# ESP32_module_desing.net
KiCad netlist of a schematic drawn in Altium Designer
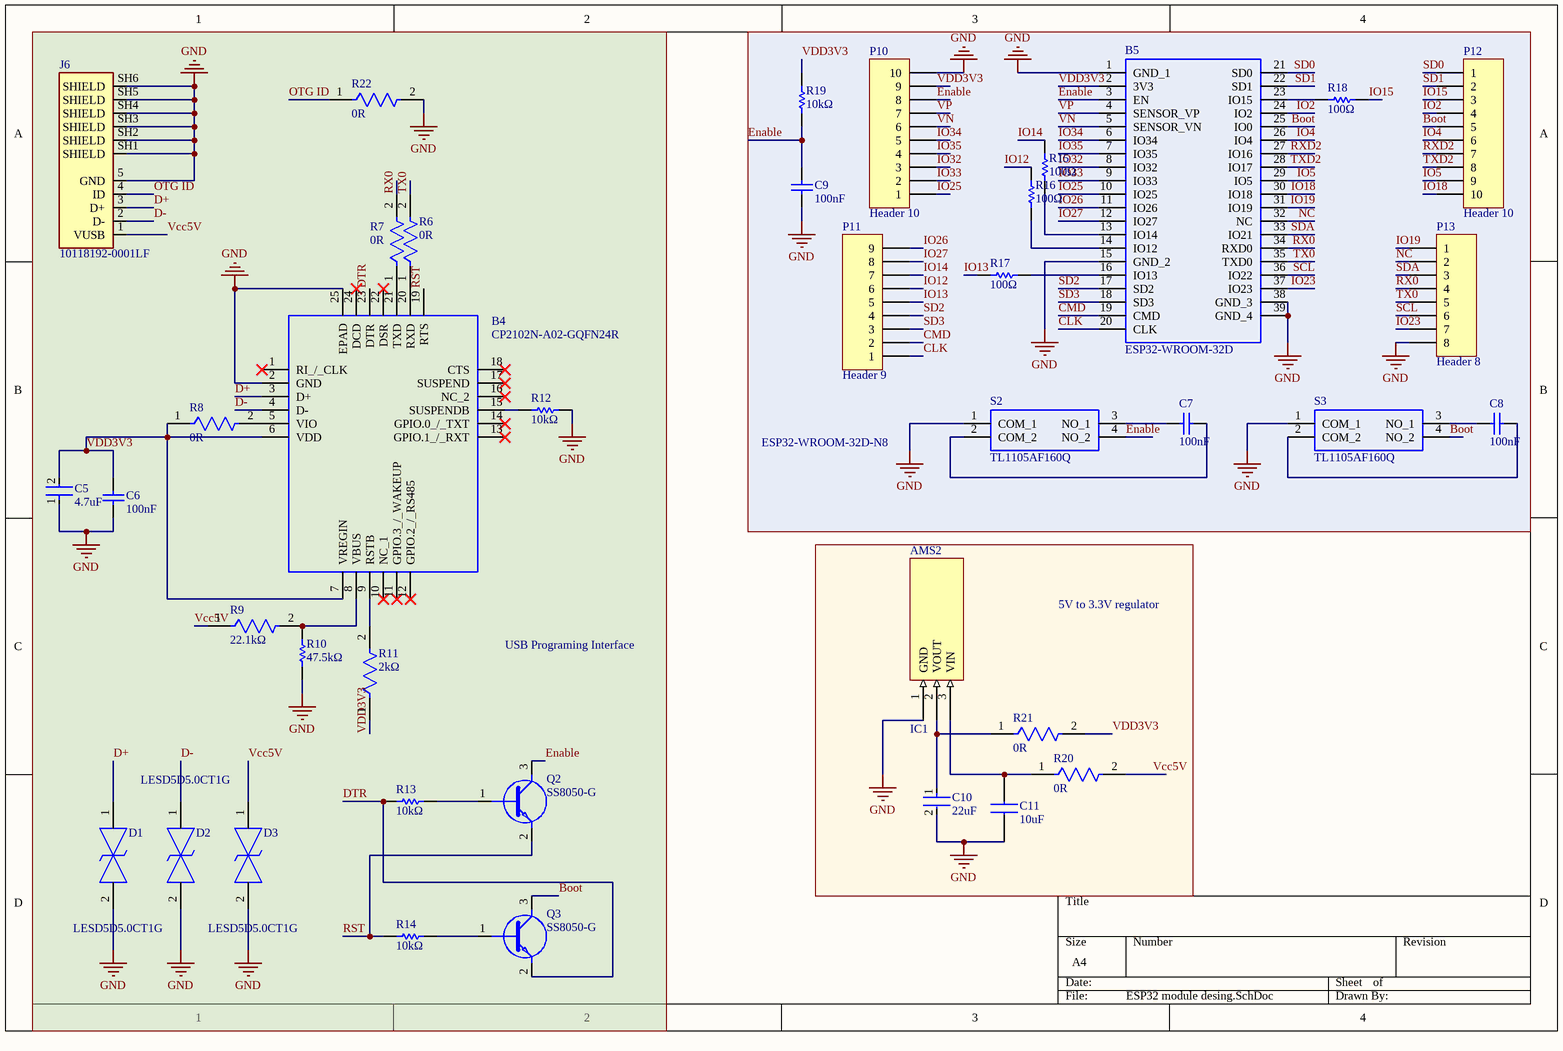
[diagram p0: ESP32 module desing.SchDoc]

(export (version "E")
  (design (tool "Eeschema 10.0.6"))
  (components
    (comp (ref "AMS2")
      (value "IC1")
      (footprint "SOT89-150P350X150-3N")
      (fields
        (field (name "MANUFACTURER") "YONGYUTAI")
        (field (name "MFR. PART #") "AMS1117-3.3")
        (field (name "LCSC PART #") "C2904742")
      )
      (libsource (lib "AMS1117-3.3") (part "IC?"))
    )
    (comp (ref "B4")
      (value "CP2102N-A02-GQFN24R")
      (footprint "QFN50P400X400X80-25N-D")
      (description "USB Interface IC USB to UART bridge - QFN24")
      (fields (field (name "MANUFACTURER") "SILICON LABS") (field (name "LCSC PART#") "C969151"))
      (libsource (lib "CP2102N-A02-GQFN24R") (part "CP2102N-A02-GQFN24R"))
    )
    (comp (ref "B5")
      (value "ESP32-WROOM-32D")
      (footprint "ESP32WROOM32D")
      (description "WiFi Modules (802.11) SMD Module, ESP32-D0WD, 32Mbits SPI flash, UART mode, PCB antenna")
      (libsource (lib "ESP32-WROOM-32D") (part "ESP32-WROOM-32D"))
    )
    (comp (ref "C5")
      (value "4.7uF")
      (footprint "FP-CL21-IPC_A")
      (description "X5R 25V 4.7uF ±10% 0805 Multilayer Ceramic Capacitors MLCC - SMD/SMT ROHS")
      (fields (field (name "LCSC PART#") "C1779") (field (name "MFR.PART #") "CL21A475KAQNNNE"))
      (libsource (lib "Altium Content Vault") (part "b4654b650e69147ec39a6b967a45e02"))
    )
    (comp (ref "C6")
      (value "100nF")
      (footprint "CAPC1050X55X23ML05T13")
      (description "X7R 100nF 16V ±10% 0402 Multilayer Ceramic Capacitors MLCC - SMD/SMT ROHS")
      (fields
        (field (name "MANUFACTURER") "Samsung Electro-Mechanics")
        (field (name "MFR.PART #") "CL05B104KO5NNNC")
      )
      (libsource (lib "Altium Content Vault") (part "CAP-NP-2"))
    )
    (comp (ref "C7")
      (value "100nF")
      (footprint "CAPC1050X55X23ML05T13")
      (description "X7R 100nF 16V ±10% 0402 Multilayer Ceramic Capacitors MLCC - SMD/SMT ROHS")
      (fields
        (field (name "MANUFACTURER") "Samsung Electro-Mechanics")
        (field (name "MFR.PART #") "CL05B104KO5NNNC")
      )
      (libsource (lib "Altium Content Vault") (part "CAP-NP-2"))
    )
    (comp (ref "C8")
      (value "100nF")
      (footprint "CAPC1050X55X23ML05T13")
      (description "X7R 100nF 16V ±10% 0402 Multilayer Ceramic Capacitors MLCC - SMD/SMT ROHS")
      (fields
        (field (name "MANUFACTURER") "Samsung Electro-Mechanics")
        (field (name "MFR.PART #") "CL05B104KO5NNNC")
      )
      (libsource (lib "Altium Content Vault") (part "CAP-NP-2"))
    )
    (comp (ref "C9")
      (value "100nF")
      (footprint "CAPC1050X55X23ML05T13")
      (description "X7R 100nF 16V ±10% 0402 Multilayer Ceramic Capacitors MLCC - SMD/SMT ROHS")
      (fields
        (field (name "MANUFACTURER") "Samsung Electro-Mechanics")
        (field (name "MFR.PART #") "CL05B104KO5NNNC")
      )
      (libsource (lib "Altium Content Vault") (part "CAP-NP-2"))
    )
    (comp (ref "C10")
      (value "22uF")
      (footprint "FP-GRM219-0_2-0_15-IPC_A")
      (description "Chip Multilayer Ceramic Capacitors for General Purpose, 0805, 22uF, X5R, 15%, 20%, 16V")
      (fields (field (name "MFR. PART #") "GRM219R61C226ME15L") (field (name "LCSC PART #") "C162295"))
      (libsource (lib "Altium Content Vault") (part "b4654b650e69147ec39a6b967a45e02"))
    )
    (comp (ref "C11")
      (value "10uF")
      (footprint "CAPC1005X70N")
      (description "6.3V 10uF X5R ±20% 0402 Multilayer Ceramic Capacitors MLCC - SMD/SMT ROHS")
      (fields
        (field (name "MANUFACTURER") "Samsung Electro-Mechanics")
        (field (name "MFR. PART #") "CL05A106MQ5NUNC")
      )
      (libsource (lib "CL05A106MQ5NUNC") (part "CL05A106MQ5NUNC"))
    )
    (comp (ref "D1")
      (value "LESD5D5.0CT1G")
      (footprint "LESD5D50CT1G")
      (description "Transient Voltage Suppressors for ESD Protection")
      (fields
        (field (name "MANUFACTURER") "UMW(Youtai Semiconductor Co., Ltd.)")
        (field (name "LCSC PART#") "C5199850")
      )
      (libsource (lib "LESD5D5.0CT1G") (part "LESD5D5.0CT1G"))
    )
    (comp (ref "D2")
      (value "LESD5D5.0CT1G")
      (footprint "LESD5D50CT1G")
      (description "Transient Voltage Suppressors for ESD Protection")
      (fields
        (field (name "MANUFACTURER") "UMW(Youtai Semiconductor Co., Ltd.)")
        (field (name "LCSC PART#") "C5199850")
      )
      (libsource (lib "LESD5D5.0CT1G") (part "LESD5D5.0CT1G"))
    )
    (comp (ref "D3")
      (value "LESD5D5.0CT1G")
      (footprint "LESD5D50CT1G")
      (description "Transient Voltage Suppressors for ESD Protection")
      (fields
        (field (name "MANUFACTURER") "UMW(Youtai Semiconductor Co., Ltd.)")
        (field (name "LCSC PART#") "C5199850")
      )
      (libsource (lib "LESD5D5.0CT1G") (part "LESD5D5.0CT1G"))
    )
    (comp (ref "J6")
      (value "10118192-0001LF")
      (footprint "AMPHENOL_10118192-0001LF")
      (description "Single Port 5 Contact Horizontal Right Angle Shielded Micro B USB 2.0 Connector")
      (fields (field (name "LCSC PART#") "C132564") (field (name "MANUFACTURER") "Amphenol ICC"))
      (libsource (lib "10118192-0001LF") (part "10118192-0001LF"))
    )
    (comp (ref "P10")
      (value "Header 10")
      (footprint "HDR1X10")
      (description "Header, 10-Pin")
      (fields (field (name "PUBLISHER") "Altium Limited"))
      (libsource (lib "Miscellaneous Connectors") (part "Header 10"))
    )
    (comp (ref "P11")
      (value "Header 9")
      (footprint "HDR1X9")
      (description "Header, 9-Pin")
      (fields (field (name "PUBLISHER") "Altium Limited"))
      (libsource (lib "Miscellaneous Connectors") (part "Header 9"))
    )
    (comp (ref "P12")
      (value "Header 10")
      (footprint "HDR1X10")
      (description "Header, 10-Pin")
      (fields (field (name "PUBLISHER") "Altium Limited"))
      (libsource (lib "") (part "Header 10_1"))
    )
    (comp (ref "P13")
      (value "Header 8")
      (footprint "HDR1X8")
      (description "Header, 8-Pin")
      (fields (field (name "PUBLISHER") "Altium Limited"))
      (libsource (lib "Miscellaneous Connectors") (part "Header 8"))
    )
    (comp (ref "Q2")
      (value "SS8050-G")
      (footprint "SOT95P240X115-3N")
      (fields
        (field (name "MANUFACTURER") "Jiangsu Changjing Electronics Technology Co., Ltd.")
        (field (name "LCSC PART#") "C164885")
      )
      (libsource (lib "SS8050-G") (part "SS8050-G"))
    )
    (comp (ref "Q3")
      (value "SS8050-G")
      (footprint "SOT95P240X115-3N")
      (fields
        (field (name "MANUFACTURER") "Jiangsu Changjing Electronics Technology Co., Ltd.")
        (field (name "LCSC PART#") "C164885")
      )
      (libsource (lib "SS8050-G") (part "SS8050-G"))
    )
    (comp (ref "R6")
      (value "0R")
      (footprint "FP-RC0402-0_4-IPC_A")
      (description "RES SMD 0 OHM JUMPER 1/16W 0402")
      (fields (field (name "MANUFACTURER") "Yageo") (field (name "LCSC PART #") "C106231"))
      (libsource (lib "Altium Content Vault") (part "1029c3af85768c4190bb7ad29bc67b5"))
    )
    (comp (ref "R7")
      (value "0R")
      (footprint "FP-RC0402-0_4-IPC_A")
      (description "RES SMD 0 OHM JUMPER 1/16W 0402")
      (fields (field (name "MANUFACTURER") "Yageo") (field (name "LCSC PART #") "C106231"))
      (libsource (lib "Altium Content Vault") (part "1029c3af85768c4190bb7ad29bc67b5"))
    )
    (comp (ref "R8")
      (value "0R")
      (footprint "FP-RC0402-0_4-IPC_A")
      (description "RES SMD 0 OHM JUMPER 1/16W 0402")
      (fields (field (name "MANUFACTURER") "Yageo") (field (name "LCSC PART #") "C106231"))
      (libsource (lib "Altium Content Vault") (part "1029c3af85768c4190bb7ad29bc67b5"))
    )
    (comp (ref "R9")
      (value "22.1kΩ")
      (footprint "FP-RC0402-0_4-IPC_B")
      (description "RES 22.1K OHM 1% 1/16W 0402")
      (fields (field (name "LCSC PART#") "C163478") (field (name "MANUFACTURER") "YAGEO"))
      (libsource (lib "Altium Content Vault") (part "1029c3af85768c4190bb7ad29bc67b5"))
    )
    (comp (ref "R10")
      (value "47.5kΩ")
      (footprint "RESC1005X40X25NL05T10")
      (fields
        (field (name "MFR.PART #") "RC0402FR-0747K5L")
        (field (name "MANUFACTURER") "YAGEO")
        (field (name "LCSC PART#") "C137974")
      )
      (libsource (lib "Altium Content Vault") (part "RES"))
    )
    (comp (ref "R11")
      (value "2kΩ")
      (footprint "FP-RC_L0402-MFG")
      (fields
        (field (name "LCSC PART#") "C60488")
        (field (name "MANUFACTURER") "YAGEO")
        (field (name "MFR.PART #") "RESC10050X35")
      )
      (libsource (lib "Altium Content Vault") (part "1029c3af85768c4190bb7ad29bc67b5"))
    )
    (comp (ref "R12")
      (value "10kΩ")
      (footprint "RESC1005X40X25LL05T10")
      (fields
        (field (name "MFR.PART #") "RC0402FR-0710KL")
        (field (name "MANUFACTURER") "YAGEO")
        (field (name "LCSC PART#") "C60490")
      )
      (libsource (lib "Altium Content Vault") (part "RES"))
    )
    (comp (ref "R13")
      (value "10kΩ")
      (footprint "RESC1005X40X25LL05T10")
      (fields
        (field (name "MFR.PART #") "RC0402FR-0710KL")
        (field (name "MANUFACTURER") "YAGEO")
        (field (name "LCSC PART#") "C60490")
      )
      (libsource (lib "Altium Content Vault") (part "RES"))
    )
    (comp (ref "R14")
      (value "10kΩ")
      (footprint "RESC1005X40X25LL05T10")
      (fields
        (field (name "MFR.PART #") "RC0402FR-0710KL")
        (field (name "MANUFACTURER") "YAGEO")
        (field (name "LCSC PART#") "C60490")
      )
      (libsource (lib "Altium Content Vault") (part "RES"))
    )
    (comp (ref "R15")
      (value "100Ω")
      (footprint "RESC1005X40X25ML05T10")
      (description "100Ω 62.5mW 50V ±1% -55℃~+155℃ ±100ppm/℃ 0402 Chip Resistor - Surface Mount ROHS")
      (fields (field (name "MFR.PART #") "RC0402FR-07100RL") (field (name "MANUFACTURER") "YAGEO"))
      (libsource (lib "Altium Content Vault") (part "RES"))
    )
    (comp (ref "R16")
      (value "100Ω")
      (footprint "RESC1005X40X25ML05T10")
      (description "100Ω 62.5mW 50V ±1% -55℃~+155℃ ±100ppm/℃ 0402 Chip Resistor - Surface Mount ROHS")
      (fields (field (name "MFR.PART #") "RC0402FR-07100RL") (field (name "MANUFACTURER") "YAGEO"))
      (libsource (lib "Altium Content Vault") (part "RES"))
    )
    (comp (ref "R17")
      (value "100Ω")
      (footprint "RESC1005X40X25ML05T10")
      (description "100Ω 62.5mW 50V ±1% -55℃~+155℃ ±100ppm/℃ 0402 Chip Resistor - Surface Mount ROHS")
      (fields (field (name "MFR.PART #") "RC0402FR-07100RL") (field (name "MANUFACTURER") "YAGEO"))
      (libsource (lib "Altium Content Vault") (part "RES"))
    )
    (comp (ref "R18")
      (value "100Ω")
      (footprint "RESC1005X40X25ML05T10")
      (description "100Ω 62.5mW 50V ±1% -55℃~+155℃ ±100ppm/℃ 0402 Chip Resistor - Surface Mount ROHS")
      (fields (field (name "MFR.PART #") "RC0402FR-07100RL") (field (name "MANUFACTURER") "YAGEO"))
      (libsource (lib "Altium Content Vault") (part "RES"))
    )
    (comp (ref "R19")
      (value "10kΩ")
      (footprint "RESC1005X40X25LL05T10")
      (fields
        (field (name "MFR.PART #") "RC0402FR-0710KL")
        (field (name "MANUFACTURER") "YAGEO")
        (field (name "LCSC PART#") "C60490")
      )
      (libsource (lib "Altium Content Vault") (part "RES"))
    )
    (comp (ref "R20")
      (value "0R")
      (footprint "FP-RC0402-0_4-IPC_A")
      (description "RES SMD 0 OHM JUMPER 1/16W 0402")
      (fields (field (name "MANUFACTURER") "Yageo") (field (name "LCSC PART #") "C106231"))
      (libsource (lib "Altium Content Vault") (part "1029c3af85768c4190bb7ad29bc67b5"))
    )
    (comp (ref "R21")
      (value "0R")
      (footprint "FP-RC0402-0_4-IPC_A")
      (description "RES SMD 0 OHM JUMPER 1/16W 0402")
      (fields (field (name "MANUFACTURER") "Yageo") (field (name "LCSC PART #") "C106231"))
      (libsource (lib "Altium Content Vault") (part "1029c3af85768c4190bb7ad29bc67b5"))
    )
    (comp (ref "R22")
      (value "0R")
      (footprint "FP-RC0402-0_4-IPC_A")
      (description "RES SMD 0 OHM JUMPER 1/16W 0402")
      (fields (field (name "MANUFACTURER") "Yageo") (field (name "LCSC PART #") "C106231"))
      (libsource (lib "Altium Content Vault") (part "1029c3af85768c4190bb7ad29bc67b5"))
    )
    (comp (ref "S2")
      (value "TL1105AF160Q")
      (footprint "TL1105AF160Q")
      (description "6mm 1.4mm Round Button 50mA Straight 6mm SPST 12V Plugin,6x6mm Tactile Switches ROHS")
      (fields (field (name "MANUFACTURER") "E-Switch") (field (name "LCSC PART#") "C273465"))
      (libsource (lib "TL1105AF160Q") (part "TL1105AF160Q"))
    )
    (comp (ref "S3")
      (value "TL1105AF160Q")
      (footprint "TL1105AF160Q")
      (description "6mm 1.4mm Round Button 50mA Straight 6mm SPST 12V Plugin,6x6mm Tactile Switches ROHS")
      (fields (field (name "MANUFACTURER") "E-Switch") (field (name "LCSC PART#") "C273465"))
      (libsource (lib "TL1105AF160Q") (part "TL1105AF160Q"))
    )
  )
  (nets
    (net (code "1") (name "/Boot") (class "Default")
      (node (ref "B5") (pin "25") (pinfunction "IO0_25") (pintype "passive"))
      (node (ref "P12") (pin "5") (pinfunction "5_5") (pintype "passive"))
      (node (ref "Q3") (pin "3") (pinfunction "C_3") (pintype "passive"))
      (node (ref "S3") (pin "4") (pinfunction "NO_2_4") (pintype "passive"))
    )
    (net (code "2") (name "/CLK") (class "Default")
      (node (ref "B5") (pin "20") (pinfunction "CLK_20") (pintype "passive"))
      (node (ref "P11") (pin "1") (pinfunction "1_1") (pintype "passive"))
    )
    (net (code "3") (name "/CMD") (class "Default")
      (node (ref "B5") (pin "19") (pinfunction "CMD_19") (pintype "passive"))
      (node (ref "P11") (pin "2") (pinfunction "2_2") (pintype "passive"))
    )
    (net (code "4") (name "/D+") (class "Default")
      (node (ref "B4") (pin "3") (pinfunction "D+_3") (pintype "passive"))
      (node (ref "D1") (pin "1") (pinfunction "1_1") (pintype "passive"))
      (node (ref "J6") (pin "3") (pinfunction "D+_3") (pintype "passive"))
    )
    (net (code "5") (name "/D-") (class "Default")
      (node (ref "B4") (pin "4") (pinfunction "D-_4") (pintype "passive"))
      (node (ref "D2") (pin "1") (pinfunction "1_1") (pintype "passive"))
      (node (ref "J6") (pin "2") (pinfunction "D-_2") (pintype "passive"))
    )
    (net (code "6") (name "/DTR") (class "Default")
      (node (ref "B4") (pin "23") (pinfunction "DTR_23") (pintype "passive"))
      (node (ref "Q3") (pin "2") (pinfunction "E_2") (pintype "passive"))
      (node (ref "R13") (pin "1") (pinfunction "1_1") (pintype "passive"))
    )
    (net (code "7") (name "/Enable") (class "Default")
      (node (ref "B5") (pin "3") (pinfunction "EN_3") (pintype "passive"))
      (node (ref "C9") (pin "1") (pinfunction "1_1") (pintype "passive"))
      (node (ref "P10") (pin "8") (pinfunction "8_8") (pintype "passive"))
      (node (ref "Q2") (pin "3") (pinfunction "C_3") (pintype "passive"))
      (node (ref "R19") (pin "1") (pinfunction "1_1") (pintype "passive"))
      (node (ref "S2") (pin "4") (pinfunction "NO_2_4") (pintype "passive"))
    )
    (net (code "8") (name "/IO2") (class "Default")
      (node (ref "B5") (pin "24") (pinfunction "IO2_24") (pintype "passive"))
      (node (ref "P12") (pin "4") (pinfunction "4_4") (pintype "passive"))
    )
    (net (code "9") (name "/IO4") (class "Default")
      (node (ref "B5") (pin "26") (pinfunction "IO4_26") (pintype "passive"))
      (node (ref "P12") (pin "6") (pinfunction "6_6") (pintype "passive"))
    )
    (net (code "10") (name "/IO5") (class "Default")
      (node (ref "B5") (pin "29") (pinfunction "IO5_29") (pintype "passive"))
      (node (ref "P12") (pin "9") (pinfunction "9_9") (pintype "passive"))
    )
    (net (code "11") (name "/IO12") (class "Default")
      (node (ref "P11") (pin "6") (pinfunction "6_6") (pintype "passive"))
      (node (ref "R16") (pin "2") (pinfunction "2_2") (pintype "passive"))
    )
    (net (code "12") (name "/IO13") (class "Default")
      (node (ref "P11") (pin "5") (pinfunction "5_5") (pintype "passive"))
      (node (ref "R17") (pin "1") (pinfunction "1_1") (pintype "passive"))
    )
    (net (code "13") (name "/IO14") (class "Default")
      (node (ref "P11") (pin "7") (pinfunction "7_7") (pintype "passive"))
      (node (ref "R15") (pin "2") (pinfunction "2_2") (pintype "passive"))
    )
    (net (code "14") (name "/IO15") (class "Default")
      (node (ref "P12") (pin "3") (pinfunction "3_3") (pintype "passive"))
      (node (ref "R18") (pin "2") (pinfunction "2_2") (pintype "passive"))
    )
    (net (code "15") (name "/IO18") (class "Default")
      (node (ref "B5") (pin "30") (pinfunction "IO18_30") (pintype "passive"))
      (node (ref "P12") (pin "10") (pinfunction "10_10") (pintype "passive"))
    )
    (net (code "16") (name "/IO19") (class "Default")
      (node (ref "B5") (pin "31") (pinfunction "IO19_31") (pintype "passive"))
      (node (ref "P13") (pin "1") (pinfunction "1_1") (pintype "passive"))
    )
    (net (code "17") (name "/IO23") (class "Default")
      (node (ref "B5") (pin "37") (pinfunction "IO23_37") (pintype "passive"))
      (node (ref "P13") (pin "7") (pinfunction "7_7") (pintype "passive"))
    )
    (net (code "18") (name "/IO25") (class "Default")
      (node (ref "B5") (pin "10") (pinfunction "IO25_10") (pintype "passive"))
      (node (ref "P10") (pin "1") (pinfunction "1_1") (pintype "passive"))
    )
    (net (code "19") (name "/IO26") (class "Default")
      (node (ref "B5") (pin "11") (pinfunction "IO26_11") (pintype "passive"))
      (node (ref "P11") (pin "9") (pinfunction "9_9") (pintype "passive"))
    )
    (net (code "20") (name "/IO27") (class "Default")
      (node (ref "B5") (pin "12") (pinfunction "IO27_12") (pintype "passive"))
      (node (ref "P11") (pin "8") (pinfunction "8_8") (pintype "passive"))
    )
    (net (code "21") (name "/IO32") (class "Default")
      (node (ref "B5") (pin "8") (pinfunction "IO32_8") (pintype "passive"))
      (node (ref "P10") (pin "3") (pinfunction "3_3") (pintype "passive"))
    )
    (net (code "22") (name "/IO33") (class "Default")
      (node (ref "B5") (pin "9") (pinfunction "IO33_9") (pintype "passive"))
      (node (ref "P10") (pin "2") (pinfunction "2_2") (pintype "passive"))
    )
    (net (code "23") (name "/IO34") (class "Default")
      (node (ref "B5") (pin "6") (pinfunction "IO34_6") (pintype "passive"))
      (node (ref "P10") (pin "5") (pinfunction "5_5") (pintype "passive"))
    )
    (net (code "24") (name "/IO35") (class "Default")
      (node (ref "B5") (pin "7") (pinfunction "IO35_7") (pintype "passive"))
      (node (ref "P10") (pin "4") (pinfunction "4_4") (pintype "passive"))
    )
    (net (code "25") (name "/NC") (class "Default")
      (node (ref "B5") (pin "32") (pinfunction "NC_32") (pintype "passive"))
      (node (ref "P13") (pin "2") (pinfunction "2_2") (pintype "passive"))
    )
    (net (code "26") (name "/OTG ID") (class "Default")
      (node (ref "J6") (pin "4") (pinfunction "ID_4") (pintype "passive"))
      (node (ref "R22") (pin "1") (pinfunction "1_1") (pintype "passive"))
    )
    (net (code "27") (name "/RST") (class "Default")
      (node (ref "B4") (pin "19") (pinfunction "RTS_19") (pintype "passive"))
      (node (ref "Q2") (pin "2") (pinfunction "E_2") (pintype "passive"))
      (node (ref "R14") (pin "1") (pinfunction "1_1") (pintype "passive"))
    )
    (net (code "28") (name "/RX0") (class "Default")
      (node (ref "B5") (pin "34") (pinfunction "RXD0_34") (pintype "passive"))
      (node (ref "P13") (pin "4") (pinfunction "4_4") (pintype "passive"))
      (node (ref "R7") (pin "2") (pinfunction "2_2") (pintype "passive"))
    )
    (net (code "29") (name "/RXD2") (class "Default")
      (node (ref "B5") (pin "27") (pinfunction "IO16_27") (pintype "passive"))
      (node (ref "P12") (pin "7") (pinfunction "7_7") (pintype "passive"))
    )
    (net (code "30") (name "/SCL") (class "Default")
      (node (ref "B5") (pin "36") (pinfunction "IO22_36") (pintype "passive"))
      (node (ref "P13") (pin "6") (pinfunction "6_6") (pintype "passive"))
    )
    (net (code "31") (name "/SD0") (class "Default")
      (node (ref "B5") (pin "21") (pinfunction "SD0_21") (pintype "passive"))
      (node (ref "P12") (pin "1") (pinfunction "1_1") (pintype "passive"))
    )
    (net (code "32") (name "/SD1") (class "Default")
      (node (ref "B5") (pin "22") (pinfunction "SD1_22") (pintype "passive"))
      (node (ref "P12") (pin "2") (pinfunction "2_2") (pintype "passive"))
    )
    (net (code "33") (name "/SD2") (class "Default")
      (node (ref "B5") (pin "17") (pinfunction "SD2_17") (pintype "passive"))
      (node (ref "P11") (pin "4") (pinfunction "4_4") (pintype "passive"))
    )
    (net (code "34") (name "/SD3") (class "Default")
      (node (ref "B5") (pin "18") (pinfunction "SD3_18") (pintype "passive"))
      (node (ref "P11") (pin "3") (pinfunction "3_3") (pintype "passive"))
    )
    (net (code "35") (name "/SDA") (class "Default")
      (node (ref "B5") (pin "33") (pinfunction "IO21_33") (pintype "passive"))
      (node (ref "P13") (pin "3") (pinfunction "3_3") (pintype "passive"))
    )
    (net (code "36") (name "/TX0") (class "Default")
      (node (ref "B5") (pin "35") (pinfunction "TXD0_35") (pintype "passive"))
      (node (ref "P13") (pin "5") (pinfunction "5_5") (pintype "passive"))
      (node (ref "R6") (pin "2") (pinfunction "2_2") (pintype "passive"))
    )
    (net (code "37") (name "/TXD2") (class "Default")
      (node (ref "B5") (pin "28") (pinfunction "IO17_28") (pintype "passive"))
      (node (ref "P12") (pin "8") (pinfunction "8_8") (pintype "passive"))
    )
    (net (code "38") (name "/VDD3V3") (class "Default")
      (node (ref "B4") (pin "6") (pinfunction "VDD_6") (pintype "passive"))
      (node (ref "B4") (pin "7") (pinfunction "VREGIN_7") (pintype "passive"))
      (node (ref "B5") (pin "2") (pinfunction "3V3_2") (pintype "passive"))
      (node (ref "C5") (pin "2") (pinfunction "2_2") (pintype "passive"))
      (node (ref "C6") (pin "2") (pinfunction "2_2") (pintype "passive"))
      (node (ref "P10") (pin "9") (pinfunction "9_9") (pintype "passive"))
      (node (ref "R11") (pin "1") (pinfunction "1_1") (pintype "passive"))
      (node (ref "R19") (pin "2") (pinfunction "2_2") (pintype "passive"))
      (node (ref "R21") (pin "2") (pinfunction "2_2") (pintype "passive"))
      (node (ref "R8") (pin "1") (pinfunction "1_1") (pintype "passive"))
    )
    (net (code "39") (name "/VN") (class "Default")
      (node (ref "B5") (pin "5") (pinfunction "SENSOR_VN_5") (pintype "passive"))
      (node (ref "P10") (pin "6") (pinfunction "6_6") (pintype "passive"))
    )
    (net (code "40") (name "/VP") (class "Default")
      (node (ref "B5") (pin "4") (pinfunction "SENSOR_VP_4") (pintype "passive"))
      (node (ref "P10") (pin "7") (pinfunction "7_7") (pintype "passive"))
    )
    (net (code "41") (name "/Vcc5V") (class "Default")
      (node (ref "D3") (pin "1") (pinfunction "1_1") (pintype "passive"))
      (node (ref "J6") (pin "1") (pinfunction "VUSB_1") (pintype "passive"))
      (node (ref "R20") (pin "2") (pinfunction "2_2") (pintype "passive"))
      (node (ref "R9") (pin "1") (pinfunction "1_1") (pintype "passive"))
    )
    (net (code "42") (name "GND") (class "Default")
      (node (ref "AMS2") (pin "1") (pinfunction "GND_1") (pintype "input"))
      (node (ref "B4") (pin "2") (pinfunction "GND_2") (pintype "passive"))
      (node (ref "B4") (pin "25") (pinfunction "EPAD_25") (pintype "passive"))
      (node (ref "B5") (pin "1") (pinfunction "GND_1_1") (pintype "passive"))
      (node (ref "B5") (pin "15") (pinfunction "GND_2_15") (pintype "passive"))
      (node (ref "B5") (pin "38") (pinfunction "GND_3_38") (pintype "passive"))
      (node (ref "B5") (pin "39") (pinfunction "GND_4_39") (pintype "passive"))
      (node (ref "C10") (pin "2") (pinfunction "2_2") (pintype "passive"))
      (node (ref "C11") (pin "1") (pinfunction "1_1") (pintype "passive"))
      (node (ref "C5") (pin "1") (pinfunction "1_1") (pintype "passive"))
      (node (ref "C6") (pin "1") (pinfunction "1_1") (pintype "passive"))
      (node (ref "C9") (pin "2") (pinfunction "2_2") (pintype "passive"))
      (node (ref "D1") (pin "2") (pinfunction "2_2") (pintype "passive"))
      (node (ref "D2") (pin "2") (pinfunction "2_2") (pintype "passive"))
      (node (ref "D3") (pin "2") (pinfunction "2_2") (pintype "passive"))
      (node (ref "J6") (pin "5") (pinfunction "GND_5") (pintype "passive"))
      (node (ref "J6") (pin "SH1") (pinfunction "SHIELD_SH1") (pintype "passive"))
      (node (ref "J6") (pin "SH2") (pinfunction "SHIELD_SH2") (pintype "passive"))
      (node (ref "J6") (pin "SH3") (pinfunction "SHIELD_SH3") (pintype "passive"))
      (node (ref "J6") (pin "SH4") (pinfunction "SHIELD_SH4") (pintype "passive"))
      (node (ref "J6") (pin "SH5") (pinfunction "SHIELD_SH5") (pintype "passive"))
      (node (ref "J6") (pin "SH6") (pinfunction "SHIELD_SH6") (pintype "passive"))
      (node (ref "P10") (pin "10") (pinfunction "10_10") (pintype "passive"))
      (node (ref "P13") (pin "8") (pinfunction "8_8") (pintype "passive"))
      (node (ref "R10") (pin "1") (pinfunction "1_1") (pintype "passive"))
      (node (ref "R12") (pin "2") (pinfunction "2_2") (pintype "passive"))
      (node (ref "R22") (pin "2") (pinfunction "2_2") (pintype "passive"))
      (node (ref "S2") (pin "1") (pinfunction "COM_1_1") (pintype "passive"))
      (node (ref "S3") (pin "1") (pinfunction "COM_1_1") (pintype "passive"))
    )
    (net (code "43") (name "Net-(AMS2-VIN)") (class "Default")
      (node (ref "AMS2") (pin "3") (pinfunction "VIN_3") (pintype "input"))
      (node (ref "C11") (pin "2") (pinfunction "2_2") (pintype "passive"))
      (node (ref "R20") (pin "1") (pinfunction "1_1") (pintype "passive"))
    )
    (net (code "44") (name "Net-(AMS2-VOUT)") (class "Default")
      (node (ref "AMS2") (pin "2") (pinfunction "VOUT_2") (pintype "input"))
      (node (ref "C10") (pin "1") (pinfunction "1_1") (pintype "passive"))
      (node (ref "R21") (pin "1") (pinfunction "1_1") (pintype "passive"))
    )
    (net (code "45") (name "Net-(B4-RSTB)") (class "Default")
      (node (ref "B4") (pin "9") (pinfunction "RSTB_9") (pintype "passive"))
      (node (ref "R11") (pin "2") (pinfunction "2_2") (pintype "passive"))
    )
    (net (code "46") (name "Net-(B4-RXD)") (class "Default")
      (node (ref "B4") (pin "20") (pinfunction "RXD_20") (pintype "passive"))
      (node (ref "R6") (pin "1") (pinfunction "1_1") (pintype "passive"))
    )
    (net (code "47") (name "Net-(B4-SUSPENDB)") (class "Default")
      (node (ref "B4") (pin "15") (pinfunction "SUSPENDB_15") (pintype "passive"))
      (node (ref "R12") (pin "1") (pinfunction "1_1") (pintype "passive"))
    )
    (net (code "48") (name "Net-(B4-TXD)") (class "Default")
      (node (ref "B4") (pin "21") (pinfunction "TXD_21") (pintype "passive"))
      (node (ref "R7") (pin "1") (pinfunction "1_1") (pintype "passive"))
    )
    (net (code "49") (name "Net-(B4-VBUS)") (class "Default")
      (node (ref "B4") (pin "8") (pinfunction "VBUS_8") (pintype "passive"))
      (node (ref "R10") (pin "2") (pinfunction "2_2") (pintype "passive"))
      (node (ref "R9") (pin "2") (pinfunction "2_2") (pintype "passive"))
    )
    (net (code "50") (name "Net-(B4-VIO)") (class "Default")
      (node (ref "B4") (pin "5") (pinfunction "VIO_5") (pintype "passive"))
      (node (ref "R8") (pin "2") (pinfunction "2_2") (pintype "passive"))
    )
    (net (code "51") (name "Net-(B5-IO12)") (class "Default")
      (node (ref "B5") (pin "14") (pinfunction "IO12_14") (pintype "passive"))
      (node (ref "R16") (pin "1") (pinfunction "1_1") (pintype "passive"))
    )
    (net (code "52") (name "Net-(B5-IO13)") (class "Default")
      (node (ref "B5") (pin "16") (pinfunction "IO13_16") (pintype "passive"))
      (node (ref "R17") (pin "2") (pinfunction "2_2") (pintype "passive"))
    )
    (net (code "53") (name "Net-(B5-IO14)") (class "Default")
      (node (ref "B5") (pin "13") (pinfunction "IO14_13") (pintype "passive"))
      (node (ref "R15") (pin "1") (pinfunction "1_1") (pintype "passive"))
    )
    (net (code "54") (name "Net-(B5-IO15)") (class "Default")
      (node (ref "B5") (pin "23") (pinfunction "IO15_23") (pintype "passive"))
      (node (ref "R18") (pin "1") (pinfunction "1_1") (pintype "passive"))
    )
    (net (code "55") (name "Net-(Q2-B)") (class "Default")
      (node (ref "Q2") (pin "1") (pinfunction "B_1") (pintype "passive"))
      (node (ref "R13") (pin "2") (pinfunction "2_2") (pintype "passive"))
    )
    (net (code "56") (name "Net-(Q3-B)") (class "Default")
      (node (ref "Q3") (pin "1") (pinfunction "B_1") (pintype "passive"))
      (node (ref "R14") (pin "2") (pinfunction "2_2") (pintype "passive"))
    )
    (net (code "57") (name "Net-(S2-COM_2)") (class "Default")
      (node (ref "C7") (pin "1") (pinfunction "1_1") (pintype "passive"))
      (node (ref "S2") (pin "2") (pinfunction "COM_2_2") (pintype "passive"))
    )
    (net (code "58") (name "Net-(S2-NO_1)") (class "Default")
      (node (ref "C7") (pin "2") (pinfunction "2_2") (pintype "passive"))
      (node (ref "S2") (pin "3") (pinfunction "NO_1_3") (pintype "passive"))
    )
    (net (code "59") (name "Net-(S3-COM_2)") (class "Default")
      (node (ref "C8") (pin "1") (pinfunction "1_1") (pintype "passive"))
      (node (ref "S3") (pin "2") (pinfunction "COM_2_2") (pintype "passive"))
    )
    (net (code "60") (name "Net-(S3-NO_1)") (class "Default")
      (node (ref "C8") (pin "2") (pinfunction "2_2") (pintype "passive"))
      (node (ref "S3") (pin "3") (pinfunction "NO_1_3") (pintype "passive"))
    )
    (net (code "61") (name "unconnected-(B4-CTS-Pad18)") (class "Default")
      (node (ref "B4") (pin "18") (pinfunction "CTS_18") (pintype "passive+no_connect"))
    )
    (net (code "62") (name "unconnected-(B4-DCD-Pad24)") (class "Default")
      (node (ref "B4") (pin "24") (pinfunction "DCD_24") (pintype "passive+no_connect"))
    )
    (net (code "63") (name "unconnected-(B4-DSR-Pad22)") (class "Default")
      (node (ref "B4") (pin "22") (pinfunction "DSR_22") (pintype "passive+no_connect"))
    )
    (net (code "64") (name "unconnected-(B4-GPIO.0_{slash}_TXT-Pad14)") (class "Default")
      (node (ref "B4") (pin "14") (pinfunction "GPIO.0_/_TXT_14") (pintype "passive+no_connect"))
    )
    (net (code "65") (name "unconnected-(B4-GPIO.1_{slash}_RXT-Pad13)") (class "Default")
      (node (ref "B4") (pin "13") (pinfunction "GPIO.1_/_RXT_13") (pintype "passive+no_connect"))
    )
    (net (code "66") (name "unconnected-(B4-GPIO.2_{slash}_RS485-Pad12)") (class "Default")
      (node (ref "B4") (pin "12") (pinfunction "GPIO.2_/_RS485_12") (pintype "passive+no_connect"))
    )
    (net (code "67") (name "unconnected-(B4-GPIO.3_{slash}_WAKEUP-Pad11)") (class "Default")
      (node (ref "B4") (pin "11") (pinfunction "GPIO.3_/_WAKEUP_11") (pintype "passive+no_connect"))
    )
    (net (code "68") (name "unconnected-(B4-NC_1-Pad10)") (class "Default")
      (node (ref "B4") (pin "10") (pinfunction "NC_1_10") (pintype "passive+no_connect"))
    )
    (net (code "69") (name "unconnected-(B4-NC_2-Pad16)") (class "Default")
      (node (ref "B4") (pin "16") (pinfunction "NC_2_16") (pintype "passive+no_connect"))
    )
    (net (code "70") (name "unconnected-(B4-RI_{slash}_CLK-Pad1)") (class "Default")
      (node (ref "B4") (pin "1") (pinfunction "RI_/_CLK_1") (pintype "passive+no_connect"))
    )
    (net (code "71") (name "unconnected-(B4-SUSPEND-Pad17)") (class "Default")
      (node (ref "B4") (pin "17") (pinfunction "SUSPEND_17") (pintype "passive+no_connect"))
    )
  )
)
